# Adafruit_BMP390.net
KiCad netlist of a schematic drawn in EAGLE
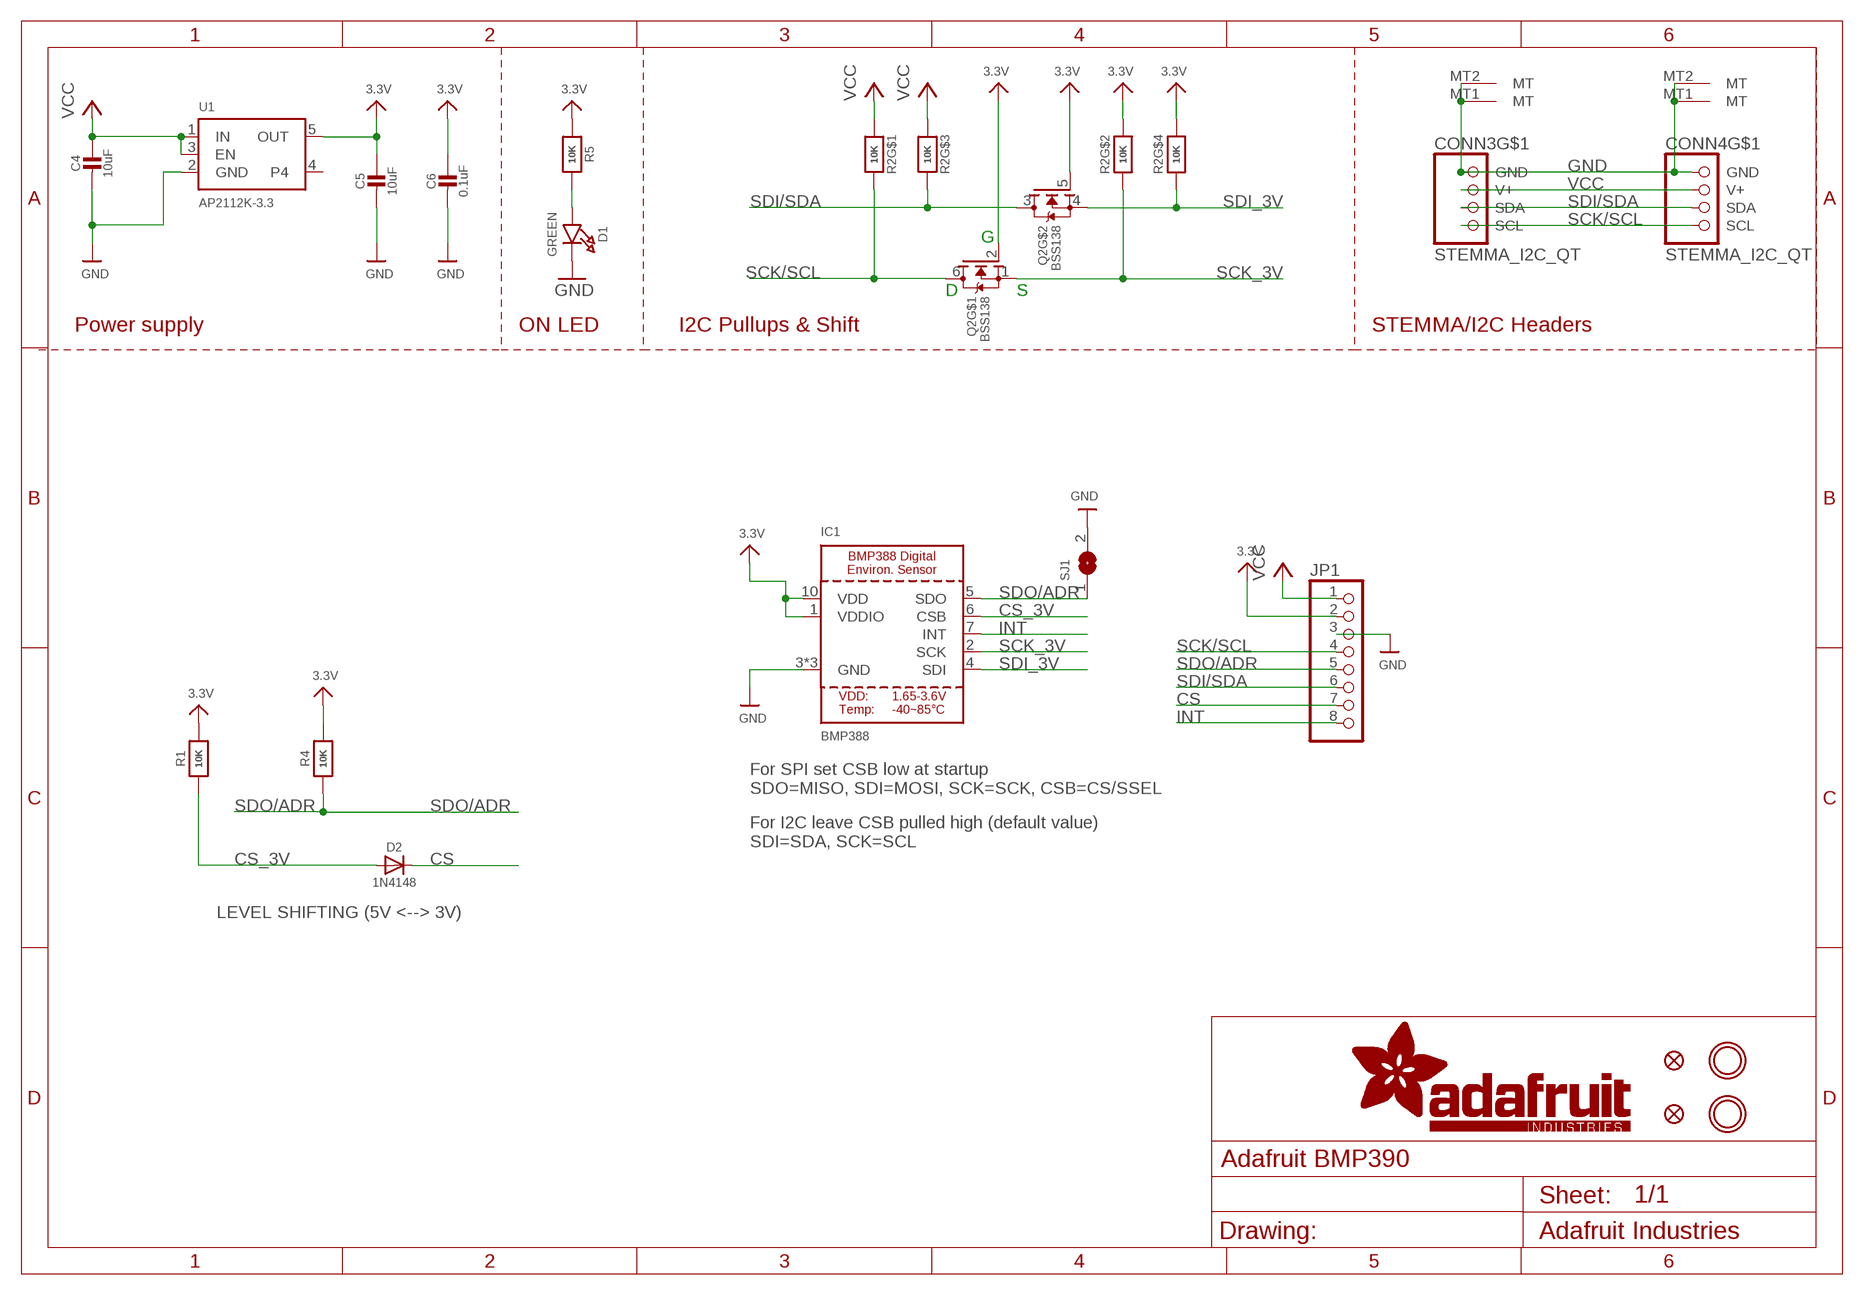
[diagram p0: schematic, sheet 1]

(export (version "E")
  (design (tool "Eeschema 10.0.6"))
  (components
    (comp (ref "C4")
      (value "10uF")
      (footprint "eagle-import:0805-NO")
      (libsource (lib "eagle-import") (part "CAP_CERAMIC0805-NOOUTLINE"))
    )
    (comp (ref "C5")
      (value "10uF")
      (footprint "eagle-import:0805-NO")
      (libsource (lib "eagle-import") (part "CAP_CERAMIC0805-NOOUTLINE"))
    )
    (comp (ref "C6")
      (value "0.1uF")
      (footprint "eagle-import:0603-NO")
      (libsource (lib "eagle-import") (part "CAP_CERAMIC0603_NO"))
    )
    (comp (ref "CONN3")
      (value "STEMMA_I2C_QT")
      (footprint "eagle-import:JST_SH4")
      (libsource (lib "eagle-import") (part "STEMMA_I2C_QT"))
    )
    (comp (ref "CONN4")
      (value "STEMMA_I2C_QT")
      (footprint "eagle-import:JST_SH4")
      (libsource (lib "eagle-import") (part "STEMMA_I2C_QT"))
    )
    (comp (ref "D1")
      (value "GREEN")
      (footprint "eagle-import:CHIPLED_0603_NOOUTLINE")
      (libsource (lib "eagle-import") (part "LED0603_NOOUTLINE"))
    )
    (comp (ref "D2")
      (value "1N4148")
      (footprint "eagle-import:SOD-323")
      (libsource (lib "eagle-import") (part "DIODESOD-323"))
    )
    (comp (ref "FID3")
      (value "FIDUCIAL_1MM")
      (footprint "eagle-import:FIDUCIAL_1MM")
      (libsource (lib "eagle-import") (part "FIDUCIAL_1MM"))
    )
    (comp (ref "FID4")
      (value "FIDUCIAL_1MM")
      (footprint "eagle-import:FIDUCIAL_1MM")
      (libsource (lib "eagle-import") (part "FIDUCIAL_1MM"))
    )
    (comp (ref "IC1")
      (value "BMP388")
      (footprint "eagle-import:BMP388")
      (libsource (lib "eagle-import") (part "BMP388"))
    )
    (comp (ref "JP1")
      (value "HEADER-1X870MIL")
      (footprint "eagle-import:1X08_ROUND_70")
      (libsource (lib "eagle-import") (part "HEADER-1X870MIL"))
    )
    (comp (ref "Q2")
      (value "BSS138")
      (footprint "eagle-import:SOT363")
      (libsource (lib "eagle-import") (part "MOSFET-N_DUAL"))
    )
    (comp (ref "R1")
      (value "10K")
      (footprint "eagle-import:0603-NO")
      (libsource (lib "eagle-import") (part "RESISTOR_0603_NOOUT"))
    )
    (comp (ref "R2")
      (value "10K")
      (footprint "eagle-import:RESPACK_4X0603")
      (libsource (lib "eagle-import") (part "RESISTOR_4PACK"))
    )
    (comp (ref "R4")
      (value "10K")
      (footprint "eagle-import:0603-NO")
      (libsource (lib "eagle-import") (part "RESISTOR_0603_NOOUT"))
    )
    (comp (ref "R5")
      (value "10K")
      (footprint "eagle-import:0603-NO")
      (libsource (lib "eagle-import") (part "RESISTOR_0603_NOOUT"))
    )
    (comp (ref "SJ1")
      (value "SOLDERJUMPER")
      (footprint "eagle-import:SOLDERJUMPER_ARROW_NOPASTE")
      (libsource (lib "eagle-import") (part "SOLDERJUMPER"))
    )
    (comp (ref "U$40")
      (value "MOUNTINGHOLE2.5")
      (footprint "eagle-import:MOUNTINGHOLE_2.5_PLATED")
      (libsource (lib "eagle-import") (part "MOUNTINGHOLE2.5"))
    )
    (comp (ref "U$41")
      (value "MOUNTINGHOLE2.5")
      (footprint "eagle-import:MOUNTINGHOLE_2.5_PLATED")
      (libsource (lib "eagle-import") (part "MOUNTINGHOLE2.5"))
    )
    (comp (ref "U1")
      (value "AP2112K-3.3")
      (footprint "eagle-import:SOT23-5")
      (libsource (lib "eagle-import") (part "VREG_SOT23-5"))
    )
  )
  (nets
    (net (code "1") (name "/CS") (class "Default")
      (node (ref "D2") (pin "C") (pinfunction "C_C") (pintype "passive"))
      (node (ref "JP1") (pin "7") (pinfunction "7_7") (pintype "passive"))
    )
    (net (code "2") (name "/CS_3V") (class "Default")
      (node (ref "D2") (pin "A") (pinfunction "A_A") (pintype "passive"))
      (node (ref "IC1") (pin "6") (pinfunction "CSB_6") (pintype "input"))
      (node (ref "R1") (pin "1") (pinfunction "1_1") (pintype "passive"))
    )
    (net (code "3") (name "/INT") (class "Default")
      (node (ref "IC1") (pin "7") (pinfunction "INT_7") (pintype "output"))
      (node (ref "JP1") (pin "8") (pinfunction "8_8") (pintype "passive"))
    )
    (net (code "4") (name "/SCK_3V") (class "Default")
      (node (ref "IC1") (pin "2") (pinfunction "SCK_2") (pintype "input"))
      (node (ref "Q2") (pin "1") (pinfunction "S_1") (pintype "bidirectional"))
      (node (ref "R2") (pin "7") (pinfunction "2_7") (pintype "passive"))
    )
    (net (code "5") (name "/SCK{slash}SCL") (class "Default")
      (node (ref "CONN3") (pin "4") (pinfunction "SCL_4") (pintype "passive"))
      (node (ref "CONN4") (pin "4") (pinfunction "SCL_4") (pintype "passive"))
      (node (ref "JP1") (pin "4") (pinfunction "4_4") (pintype "passive"))
      (node (ref "Q2") (pin "6") (pinfunction "D_6") (pintype "bidirectional"))
      (node (ref "R2") (pin "8") (pinfunction "2_8") (pintype "passive"))
    )
    (net (code "6") (name "/SDI_3V") (class "Default")
      (node (ref "IC1") (pin "4") (pinfunction "SDI_4") (pintype "input"))
      (node (ref "Q2") (pin "4") (pinfunction "S_4") (pintype "bidirectional"))
      (node (ref "R2") (pin "5") (pinfunction "2_5") (pintype "passive"))
    )
    (net (code "7") (name "/SDI{slash}SDA") (class "Default")
      (node (ref "CONN3") (pin "3") (pinfunction "SDA_3") (pintype "passive"))
      (node (ref "CONN4") (pin "3") (pinfunction "SDA_3") (pintype "passive"))
      (node (ref "JP1") (pin "6") (pinfunction "6_6") (pintype "passive"))
      (node (ref "Q2") (pin "3") (pinfunction "D_3") (pintype "bidirectional"))
      (node (ref "R2") (pin "6") (pinfunction "2_6") (pintype "passive"))
    )
    (net (code "8") (name "/SDO{slash}ADR") (class "Default")
      (node (ref "IC1") (pin "5") (pinfunction "SDO_5") (pintype "output"))
      (node (ref "JP1") (pin "5") (pinfunction "5_5") (pintype "passive"))
      (node (ref "R4") (pin "1") (pinfunction "1_1") (pintype "passive"))
      (node (ref "SJ1") (pin "1") (pinfunction "1_1") (pintype "passive"))
    )
    (net (code "9") (name "3.3V") (class "Default")
      (node (ref "C5") (pin "1") (pinfunction "1_1") (pintype "passive"))
      (node (ref "C6") (pin "1") (pinfunction "1_1") (pintype "passive"))
      (node (ref "IC1") (pin "1") (pinfunction "VDDIO_1") (pintype "power_in"))
      (node (ref "IC1") (pin "10") (pinfunction "VDD_10") (pintype "power_in"))
      (node (ref "JP1") (pin "2") (pinfunction "2_2") (pintype "passive"))
      (node (ref "Q2") (pin "2") (pinfunction "G_2") (pintype "bidirectional"))
      (node (ref "Q2") (pin "5") (pinfunction "G_5") (pintype "bidirectional"))
      (node (ref "R1") (pin "2") (pinfunction "2_2") (pintype "passive"))
      (node (ref "R2") (pin "2") (pinfunction "1_2") (pintype "passive"))
      (node (ref "R2") (pin "4") (pinfunction "1_4") (pintype "passive"))
      (node (ref "R4") (pin "2") (pinfunction "2_2") (pintype "passive"))
      (node (ref "R5") (pin "1") (pinfunction "1_1") (pintype "passive"))
      (node (ref "U1") (pin "5") (pinfunction "OUT_5") (pintype "power_in"))
    )
    (net (code "10") (name "GND") (class "Default")
      (node (ref "C4") (pin "2") (pinfunction "2_2") (pintype "passive"))
      (node (ref "C5") (pin "2") (pinfunction "2_2") (pintype "passive"))
      (node (ref "C6") (pin "2") (pinfunction "2_2") (pintype "passive"))
      (node (ref "CONN3") (pin "1") (pinfunction "GND_1") (pintype "passive"))
      (node (ref "CONN3") (pin "MT1") (pinfunction "MT_MT1") (pintype "bidirectional"))
      (node (ref "CONN3") (pin "MT2") (pinfunction "MT_MT2") (pintype "bidirectional"))
      (node (ref "CONN4") (pin "1") (pinfunction "GND_1") (pintype "passive"))
      (node (ref "CONN4") (pin "MT1") (pinfunction "MT_MT1") (pintype "bidirectional"))
      (node (ref "CONN4") (pin "MT2") (pinfunction "MT_MT2") (pintype "bidirectional"))
      (node (ref "D1") (pin "C") (pinfunction "C_C") (pintype "passive"))
      (node (ref "IC1") (pin "3") (pinfunction "GND_3") (pintype "power_in"))
      (node (ref "IC1") (pin "8") (pinfunction "GND_8") (pintype "power_in"))
      (node (ref "IC1") (pin "9") (pinfunction "GND_9") (pintype "power_in"))
      (node (ref "JP1") (pin "3") (pinfunction "3_3") (pintype "passive"))
      (node (ref "SJ1") (pin "2") (pinfunction "2_2") (pintype "passive"))
      (node (ref "U1") (pin "2") (pinfunction "GND_2") (pintype "power_in"))
    )
    (net (code "11") (name "Net-(D1-PadA)") (class "Default")
      (node (ref "D1") (pin "A") (pinfunction "A_A") (pintype "passive"))
      (node (ref "R5") (pin "2") (pinfunction "2_2") (pintype "passive"))
    )
    (net (code "12") (name "VCC") (class "Default")
      (node (ref "C4") (pin "1") (pinfunction "1_1") (pintype "passive"))
      (node (ref "CONN3") (pin "2") (pinfunction "V+_2") (pintype "passive"))
      (node (ref "CONN4") (pin "2") (pinfunction "V+_2") (pintype "passive"))
      (node (ref "JP1") (pin "1") (pinfunction "1_1") (pintype "passive"))
      (node (ref "R2") (pin "1") (pinfunction "1_1") (pintype "passive"))
      (node (ref "R2") (pin "3") (pinfunction "1_3") (pintype "passive"))
      (node (ref "U1") (pin "1") (pinfunction "IN_1") (pintype "power_in"))
      (node (ref "U1") (pin "3") (pinfunction "EN_3") (pintype "input"))
    )
    (net (code "13") (name "unconnected-(U1-P4-Pad4)") (class "Default")
      (node (ref "U1") (pin "4") (pinfunction "P4_4") (pintype "bidirectional"))
    )
  )
)
